# SparkFun_Qwiic_Barometer_LPS28DFW.net
KiCad netlist of a schematic drawn in EAGLE
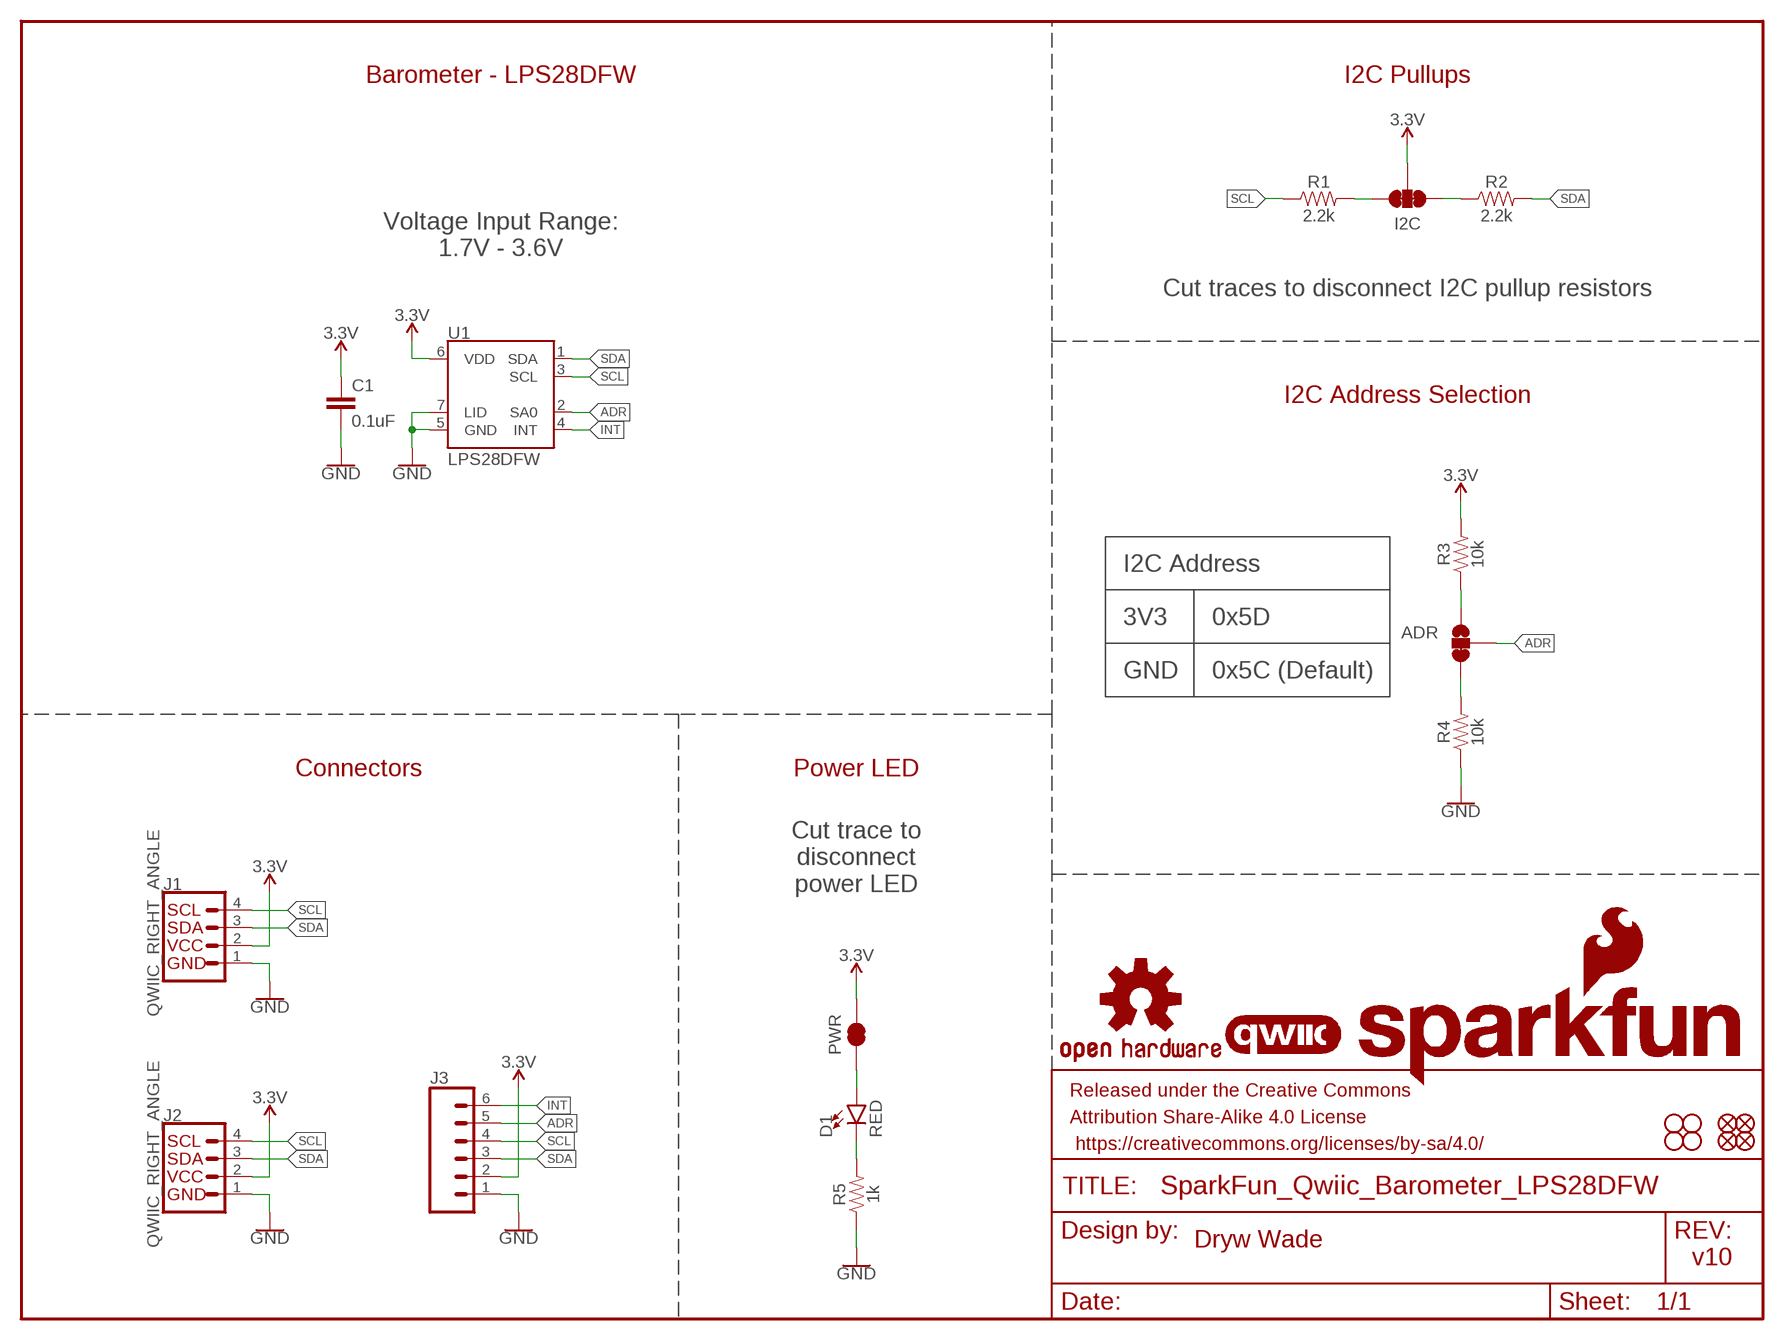
[diagram p0: schematic, sheet 1]

(export (version "E")
  (design (tool "Eeschema 10.0.6"))
  (components
    (comp (ref "ADR")
      (value "JUMPER-SMT_3_1-NC_TRACE_SILK")
      (footprint "eagle-import:SMT-JUMPER_3_1-NC_TRACE_SILK")
      (libsource (lib "eagle-import") (part "JUMPER-SMT_3_1-NC_TRACE_SILK"))
    )
    (comp (ref "C1")
      (value "0.1uF")
      (footprint "eagle-import:0603")
      (libsource (lib "eagle-import") (part "0.1UF-0603-25V-(+80/-20%)"))
    )
    (comp (ref "D1")
      (value "RED")
      (footprint "eagle-import:LED-0603")
      (libsource (lib "eagle-import") (part "LED-RED0603"))
    )
    (comp (ref "FD1")
      (value "FIDUCIAL1X2")
      (footprint "eagle-import:FIDUCIAL-1X2")
      (libsource (lib "eagle-import") (part "FIDUCIAL1X2"))
    )
    (comp (ref "FD2")
      (value "FIDUCIAL1X2")
      (footprint "eagle-import:FIDUCIAL-1X2")
      (libsource (lib "eagle-import") (part "FIDUCIAL1X2"))
    )
    (comp (ref "FD3")
      (value "FIDUCIAL1X2")
      (footprint "eagle-import:FIDUCIAL-1X2")
      (libsource (lib "eagle-import") (part "FIDUCIAL1X2"))
    )
    (comp (ref "FD4")
      (value "FIDUCIAL1X2")
      (footprint "eagle-import:FIDUCIAL-1X2")
      (libsource (lib "eagle-import") (part "FIDUCIAL1X2"))
    )
    (comp (ref "FRAME1")
      (value "FRAME-LETTER")
      (footprint "eagle-import:CREATIVE_COMMONS")
      (libsource (lib "eagle-import") (part "FRAME-LETTER"))
    )
    (comp (ref "H1")
      (value "STAND-OFF")
      (footprint "eagle-import:STAND-OFF")
      (libsource (lib "eagle-import") (part "STAND-OFF"))
    )
    (comp (ref "H2")
      (value "STAND-OFF")
      (footprint "eagle-import:STAND-OFF")
      (libsource (lib "eagle-import") (part "STAND-OFF"))
    )
    (comp (ref "H3")
      (value "STAND-OFF")
      (footprint "eagle-import:STAND-OFF")
      (libsource (lib "eagle-import") (part "STAND-OFF"))
    )
    (comp (ref "H4")
      (value "STAND-OFF")
      (footprint "eagle-import:STAND-OFF")
      (libsource (lib "eagle-import") (part "STAND-OFF"))
    )
    (comp (ref "I2C")
      (value "JUMPER-SMT_3_2-NC_TRACE_SILK")
      (footprint "eagle-import:SMT-JUMPER_3_2-NC_TRACE_SILK")
      (libsource (lib "eagle-import") (part "JUMPER-SMT_3_2-NC_TRACE_SILK"))
    )
    (comp (ref "J1")
      (value "QWIIC_RIGHT_ANGLE")
      (footprint "eagle-import:JST04_1MM_RA")
      (libsource (lib "eagle-import") (part "QWIIC_CONNECTORJS-1MM"))
    )
    (comp (ref "J2")
      (value "QWIIC_RIGHT_ANGLE")
      (footprint "eagle-import:JST04_1MM_RA")
      (libsource (lib "eagle-import") (part "QWIIC_CONNECTORJS-1MM"))
    )
    (comp (ref "J3")
      (value "CONN_06NO_SILK_NO_POP")
      (footprint "eagle-import:1X06_NO_SILK")
      (libsource (lib "eagle-import") (part "CONN_06NO_SILK_NO_POP"))
    )
    (comp (ref "LOGO1")
      (value "OSHW-LOGOS")
      (footprint "eagle-import:OSHW-LOGO-S")
      (libsource (lib "eagle-import") (part "OSHW-LOGOS"))
    )
    (comp (ref "LOGO2")
      (value "QWIIC_LOGO_5MM")
      (footprint "eagle-import:QWIIC_5MM")
      (libsource (lib "eagle-import") (part "QWIIC_LOGO_5MM"))
    )
    (comp (ref "LOGO3")
      (value "SFE_LOGO_NAME_FLAME.1_INCH")
      (footprint "eagle-import:SFE_LOGO_NAME_FLAME_.1")
      (libsource (lib "eagle-import") (part "SFE_LOGO_NAME_FLAME.1_INCH"))
    )
    (comp (ref "PWR")
      (value "JUMPER-SMT_2_NC_TRACE_SILK")
      (footprint "eagle-import:SMT-JUMPER_2_NC_TRACE_SILK")
      (libsource (lib "eagle-import") (part "JUMPER-SMT_2_NC_TRACE_SILK"))
    )
    (comp (ref "R1")
      (value "2.2k")
      (footprint "eagle-import:0603")
      (libsource (lib "eagle-import") (part "2.2KOHM-0603-1/10W-1%"))
    )
    (comp (ref "R2")
      (value "2.2k")
      (footprint "eagle-import:0603")
      (libsource (lib "eagle-import") (part "2.2KOHM-0603-1/10W-1%"))
    )
    (comp (ref "R3")
      (value "10k")
      (footprint "eagle-import:0603")
      (libsource (lib "eagle-import") (part "10KOHM-0603-1/10W-1%"))
    )
    (comp (ref "R4")
      (value "10k")
      (footprint "eagle-import:0603")
      (libsource (lib "eagle-import") (part "10KOHM-0603-1/10W-1%"))
    )
    (comp (ref "R5")
      (value "1k")
      (footprint "eagle-import:0603")
      (libsource (lib "eagle-import") (part "1KOHM-0603-1/10W-1%"))
    )
    (comp (ref "U1")
      (value "LPS28DFW")
      (footprint "eagle-import:CCLGA-7L")
      (libsource (lib "eagle-import") (part "LPS28DFW"))
    )
  )
  (nets
    (net (code "1") (name "3.3V") (class "Default")
      (node (ref "C1") (pin "1") (pinfunction "1_1") (pintype "passive"))
      (node (ref "I2C") (pin "2") (pinfunction "2_2") (pintype "passive"))
      (node (ref "J1") (pin "2") (pinfunction "2_2") (pintype "power_in"))
      (node (ref "J2") (pin "2") (pinfunction "2_2") (pintype "power_in"))
      (node (ref "J3") (pin "2") (pinfunction "2_2") (pintype "passive"))
      (node (ref "PWR") (pin "2") (pinfunction "2_2") (pintype "passive"))
      (node (ref "R3") (pin "2") (pinfunction "2_2") (pintype "passive"))
      (node (ref "U1") (pin "6") (pinfunction "VDD_6") (pintype "power_in"))
    )
    (net (code "2") (name "ADR") (class "Default")
      (node (ref "ADR") (pin "2") (pinfunction "2_2") (pintype "passive"))
      (node (ref "J3") (pin "5") (pinfunction "5_5") (pintype "passive"))
      (node (ref "U1") (pin "2") (pinfunction "SA0_2") (pintype "input"))
    )
    (net (code "3") (name "GND") (class "Default")
      (node (ref "C1") (pin "2") (pinfunction "2_2") (pintype "passive"))
      (node (ref "J1") (pin "1") (pinfunction "1_1") (pintype "power_in"))
      (node (ref "J2") (pin "1") (pinfunction "1_1") (pintype "power_in"))
      (node (ref "J3") (pin "1") (pinfunction "1_1") (pintype "passive"))
      (node (ref "R4") (pin "1") (pinfunction "1_1") (pintype "passive"))
      (node (ref "R5") (pin "1") (pinfunction "1_1") (pintype "passive"))
      (node (ref "U1") (pin "5") (pinfunction "GND_5") (pintype "power_in"))
      (node (ref "U1") (pin "7") (pinfunction "LID_7") (pintype "passive"))
    )
    (net (code "4") (name "INT") (class "Default")
      (node (ref "J3") (pin "6") (pinfunction "6_6") (pintype "passive"))
      (node (ref "U1") (pin "4") (pinfunction "INT_4") (pintype "output"))
    )
    (net (code "5") (name "Net-(ADR-Pad1)") (class "Default")
      (node (ref "ADR") (pin "1") (pinfunction "1_1") (pintype "passive"))
      (node (ref "R3") (pin "1") (pinfunction "1_1") (pintype "passive"))
    )
    (net (code "6") (name "Net-(ADR-Pad3)") (class "Default")
      (node (ref "ADR") (pin "3") (pinfunction "3_3") (pintype "passive"))
      (node (ref "R4") (pin "2") (pinfunction "2_2") (pintype "passive"))
    )
    (net (code "7") (name "Net-(D1-PadA)") (class "Default")
      (node (ref "D1") (pin "A") (pinfunction "A_A") (pintype "passive"))
      (node (ref "PWR") (pin "1") (pinfunction "1_1") (pintype "passive"))
    )
    (net (code "8") (name "Net-(D1-PadC)") (class "Default")
      (node (ref "D1") (pin "C") (pinfunction "C_C") (pintype "passive"))
      (node (ref "R5") (pin "2") (pinfunction "2_2") (pintype "passive"))
    )
    (net (code "9") (name "Net-(I2C-Pad1)") (class "Default")
      (node (ref "I2C") (pin "1") (pinfunction "1_1") (pintype "passive"))
      (node (ref "R2") (pin "1") (pinfunction "1_1") (pintype "passive"))
    )
    (net (code "10") (name "Net-(I2C-Pad3)") (class "Default")
      (node (ref "I2C") (pin "3") (pinfunction "3_3") (pintype "passive"))
      (node (ref "R1") (pin "2") (pinfunction "2_2") (pintype "passive"))
    )
    (net (code "11") (name "SCL") (class "Default")
      (node (ref "J1") (pin "4") (pinfunction "4_4") (pintype "passive"))
      (node (ref "J2") (pin "4") (pinfunction "4_4") (pintype "passive"))
      (node (ref "J3") (pin "4") (pinfunction "4_4") (pintype "passive"))
      (node (ref "R1") (pin "1") (pinfunction "1_1") (pintype "passive"))
      (node (ref "U1") (pin "3") (pinfunction "SCL_3") (pintype "input"))
    )
    (net (code "12") (name "SDA") (class "Default")
      (node (ref "J1") (pin "3") (pinfunction "3_3") (pintype "passive"))
      (node (ref "J2") (pin "3") (pinfunction "3_3") (pintype "passive"))
      (node (ref "J3") (pin "3") (pinfunction "3_3") (pintype "passive"))
      (node (ref "R2") (pin "2") (pinfunction "2_2") (pintype "passive"))
      (node (ref "U1") (pin "1") (pinfunction "SDA_1") (pintype "bidirectional"))
    )
  )
)
